# TPs.net
KiCad netlist of a schematic drawn in Altium Designer
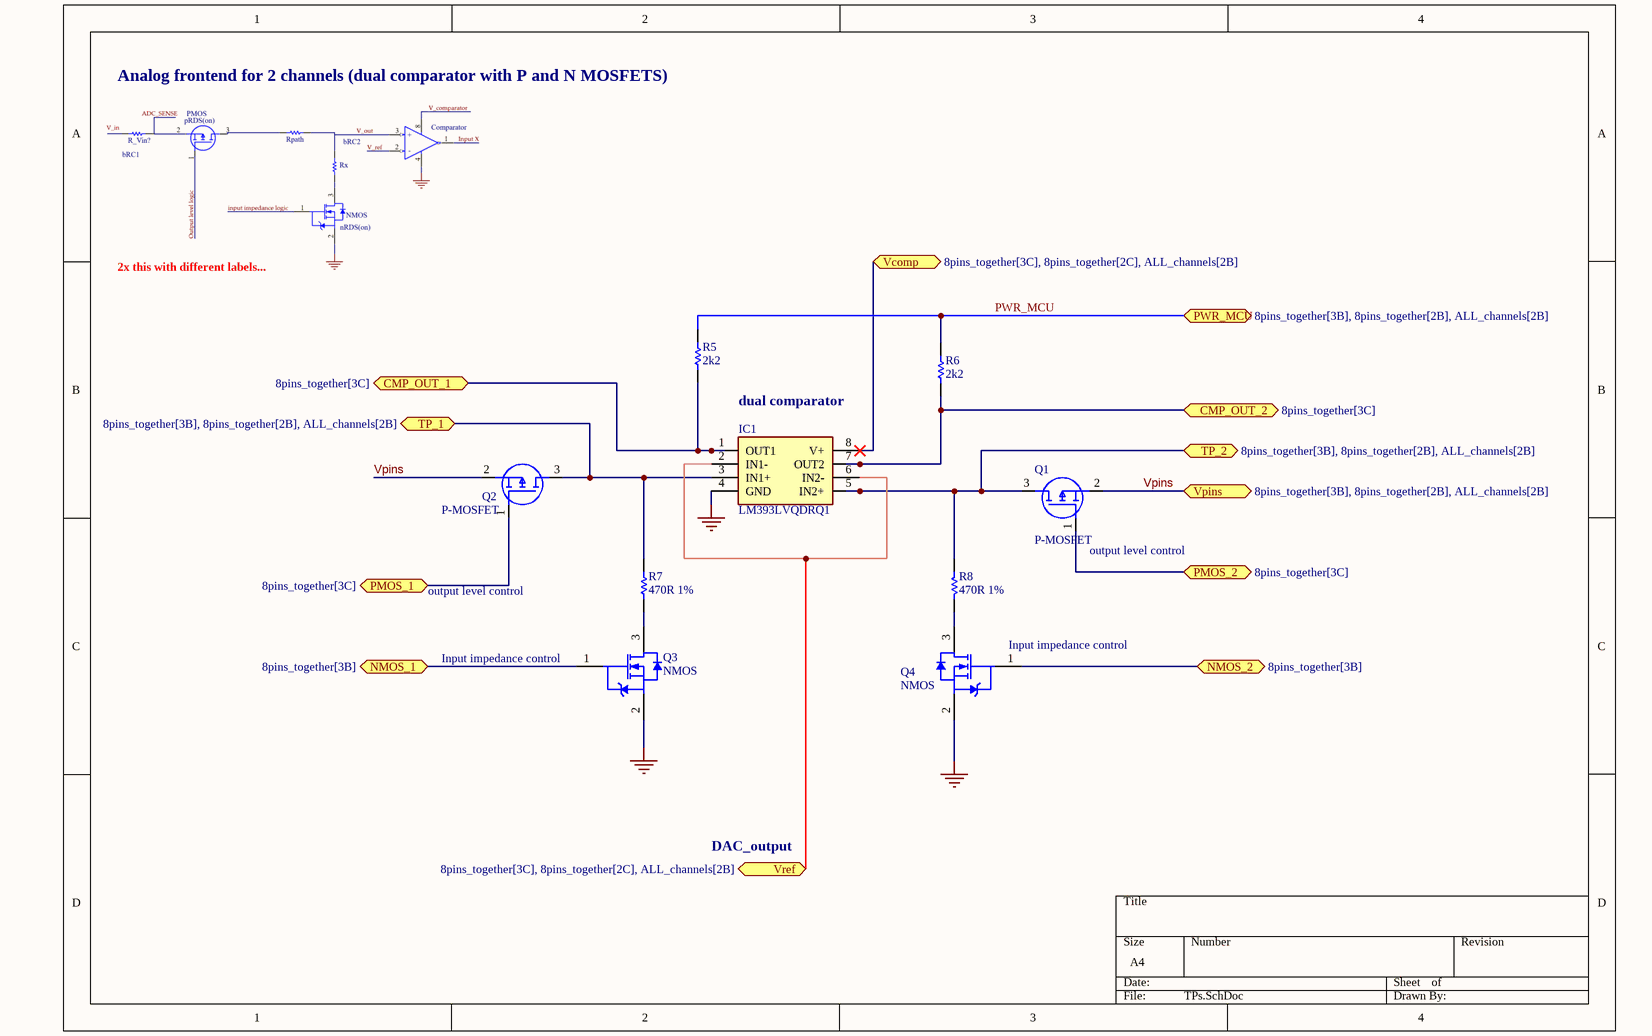
[diagram p0: TPs.SchDoc]

(export (version "E")
  (design (tool "Eeschema 10.0.6"))
  (components
    (comp (ref "IC1")
      (value "LM393LVQDRQ1")
      (footprint "PcbLib1:SOIC127P600X175-8N")
      (description "Integrated Circuit")
      (fields (field (name "MOUSER PART NUMBER") "595-LM393LVQDRQ1"))
      (libsource (lib "Schlib1") (part "LM393LVQDRQ1"))
    )
    (comp (ref "Q1")
      (value "P-MOSFET")
      (footprint "PcbLib1:SOTFL95P240X88-3N")
      (description "MOSFET (P-Channel) - low RDS on")
      (fields
        (field (name "MANUFACTURER_PART_NUMBER") "SSM3J358R,LF")
        (field (name "MOUSER PART NUMBER") "757-SSM3J358RLF")
      )
      (libsource (lib "Schlib1") (part "P-MOSFET"))
    )
    (comp (ref "Q2")
      (value "P-MOSFET")
      (footprint "PcbLib1:SOTFL95P240X88-3N")
      (description "MOSFET (P-Channel) - low RDS on")
      (fields
        (field (name "MANUFACTURER_PART_NUMBER") "SSM3J358R,LF")
        (field (name "MOUSER PART NUMBER") "757-SSM3J358RLF")
      )
      (libsource (lib "Schlib1") (part "P-MOSFET"))
    )
    (comp (ref "Q3")
      (value "NMOS")
      (footprint "PcbLib1:SOT95P240X110-3N")
      (description "N-Channel MOSFET Transistor PJA3432_R1_00001")
      (fields (field (name "MANUFACTURER") "Fairchild"))
      (libsource (lib "Schlib1") (part "N-MOSFET"))
    )
    (comp (ref "Q4")
      (value "NMOS")
      (footprint "PcbLib1:SOT95P240X110-3N")
      (description "N-Channel MOSFET Transistor PJA3432_R1_00001")
      (fields (field (name "MANUFACTURER") "Fairchild"))
      (libsource (lib "Schlib1") (part "N-MOSFET"))
    )
    (comp (ref "R5")
      (value "2k2")
      (footprint "PcbLib1:RESC1005X40X25NL05T05")
      (fields (field (name "PART NUMBER") "ERJ2RKF6800X") (field (name "MANUFACTURER") "Panasonic"))
      (libsource (lib "Schlib1") (part "Resistor 0402 100mW"))
    )
    (comp (ref "R6")
      (value "2k2")
      (footprint "PcbLib1:RESC1005X40X25NL05T05")
      (fields (field (name "PART NUMBER") "ERJ2RKF6800X") (field (name "MANUFACTURER") "Panasonic"))
      (libsource (lib "Schlib1") (part "Resistor 0402 100mW"))
    )
    (comp (ref "R7")
      (value "470R 1%")
      (footprint "PcbLib1:RESC1005X40X25NL05T05")
      (fields (field (name "PART NUMBER") "ERJ2RKF6800X") (field (name "MANUFACTURER") "Panasonic"))
      (libsource (lib "Schlib1") (part "Resistor 0402 100mW"))
    )
    (comp (ref "R8")
      (value "470R 1%")
      (footprint "PcbLib1:RESC1005X40X25NL05T05")
      (fields (field (name "PART NUMBER") "ERJ2RKF6800X") (field (name "MANUFACTURER") "Panasonic"))
      (libsource (lib "Schlib1") (part "Resistor 0402 100mW"))
    )
  )
  (nets
    (net (code "1") (name "/CMP_OUT_1") (class "Default")
      (node (ref "IC1") (pin "1") (pinfunction "OUT1_1") (pintype "passive"))
      (node (ref "R5") (pin "2") (pinfunction "2_2") (pintype "passive"))
    )
    (net (code "2") (name "/CMP_OUT_2") (class "Default")
      (node (ref "IC1") (pin "7") (pinfunction "OUT2_7") (pintype "passive"))
      (node (ref "R6") (pin "2") (pinfunction "2_2") (pintype "passive"))
    )
    (net (code "3") (name "/NMOS_1") (class "Default")
      (node (ref "Q3") (pin "1") (pinfunction "G_1") (pintype "passive"))
    )
    (net (code "4") (name "/NMOS_2") (class "Default")
      (node (ref "Q4") (pin "1") (pinfunction "G_1") (pintype "passive"))
    )
    (net (code "5") (name "/PMOS_1") (class "Default")
      (node (ref "Q2") (pin "1") (pinfunction "G_1") (pintype "passive"))
    )
    (net (code "6") (name "/PMOS_2") (class "Default")
      (node (ref "Q1") (pin "1") (pinfunction "G_1") (pintype "passive"))
    )
    (net (code "7") (name "/PWR_MCU") (class "Default")
      (node (ref "R5") (pin "1") (pinfunction "1_1") (pintype "passive"))
      (node (ref "R6") (pin "1") (pinfunction "1_1") (pintype "passive"))
    )
    (net (code "8") (name "/TP_1") (class "Default")
      (node (ref "IC1") (pin "3") (pinfunction "IN1+_3") (pintype "passive"))
      (node (ref "Q2") (pin "3") (pinfunction "D_3") (pintype "passive"))
      (node (ref "R7") (pin "1") (pinfunction "1_1") (pintype "passive"))
    )
    (net (code "9") (name "/TP_2") (class "Default")
      (node (ref "IC1") (pin "5") (pinfunction "IN2+_5") (pintype "passive"))
      (node (ref "Q1") (pin "3") (pinfunction "D_3") (pintype "passive"))
      (node (ref "R8") (pin "1") (pinfunction "1_1") (pintype "passive"))
    )
    (net (code "10") (name "/Vcomp") (class "Default")
      (node (ref "IC1") (pin "8") (pinfunction "V+_8") (pintype "passive+no_connect"))
    )
    (net (code "11") (name "/Vpins") (class "Default")
      (node (ref "Q1") (pin "2") (pinfunction "S_2") (pintype "passive"))
      (node (ref "Q2") (pin "2") (pinfunction "S_2") (pintype "passive"))
    )
    (net (code "12") (name "/Vref") (class "Default")
      (node (ref "IC1") (pin "2") (pinfunction "IN1-_2") (pintype "passive"))
      (node (ref "IC1") (pin "6") (pinfunction "IN2-_6") (pintype "passive"))
    )
    (net (code "13") (name "GND") (class "Default")
      (node (ref "IC1") (pin "4") (pinfunction "GND_4") (pintype "passive"))
      (node (ref "Q3") (pin "2") (pinfunction "S_2") (pintype "passive"))
      (node (ref "Q4") (pin "2") (pinfunction "S_2") (pintype "passive"))
    )
    (net (code "14") (name "Net-(Q3-D)") (class "Default")
      (node (ref "Q3") (pin "3") (pinfunction "D_3") (pintype "passive"))
      (node (ref "R7") (pin "2") (pinfunction "2_2") (pintype "passive"))
    )
    (net (code "15") (name "Net-(Q4-D)") (class "Default")
      (node (ref "Q4") (pin "3") (pinfunction "D_3") (pintype "passive"))
      (node (ref "R8") (pin "2") (pinfunction "2_2") (pintype "passive"))
    )
  )
)
